# medusa-AI-power.net
KiCad netlist of a schematic drawn in Altium Designer
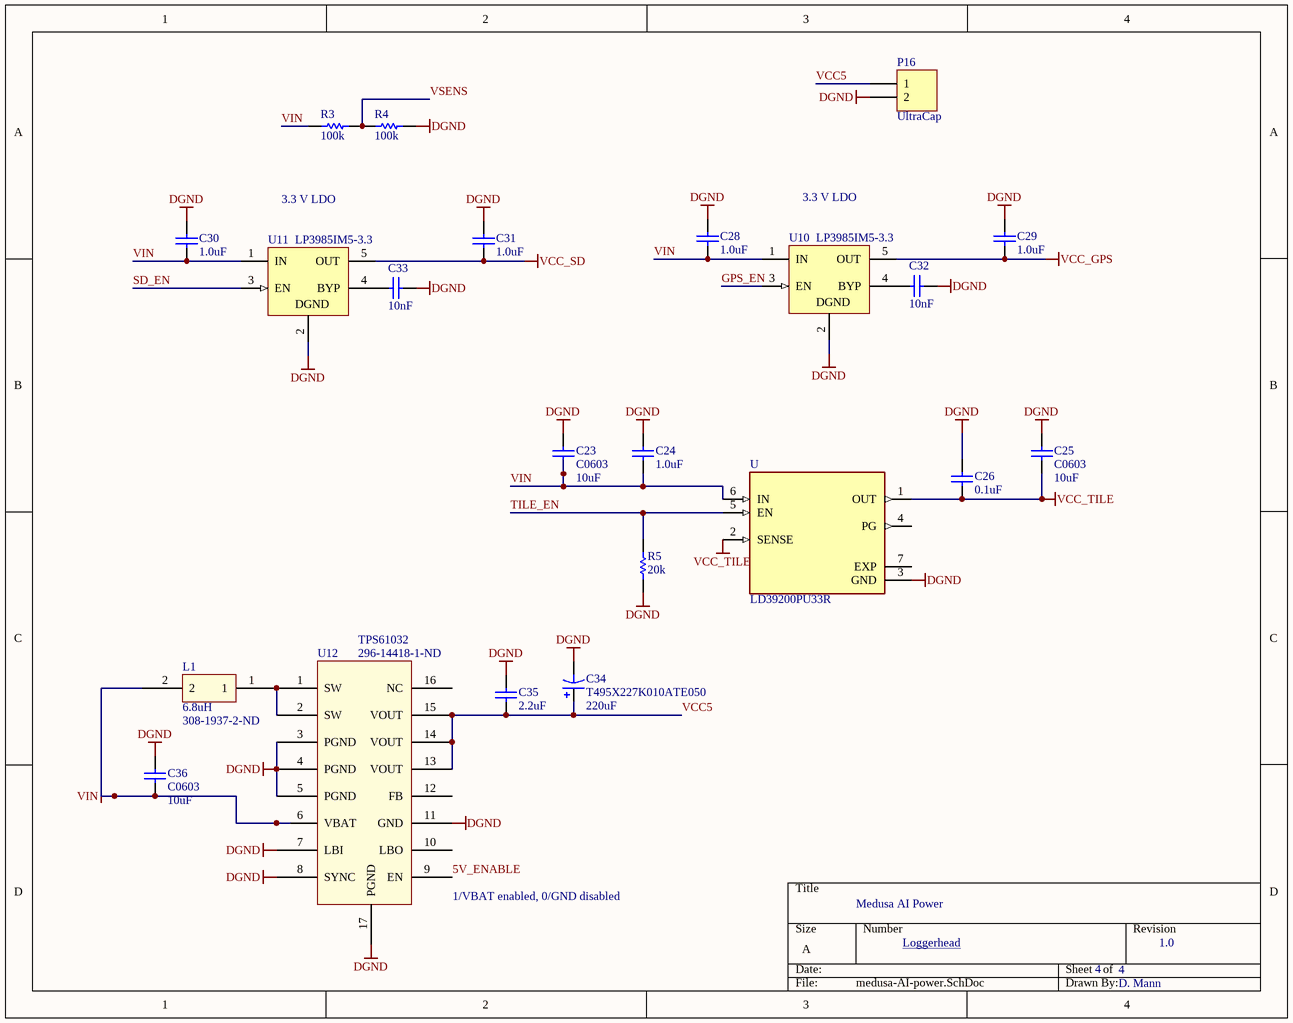
[diagram p0: medusa-AI-power.SchDoc]

(export (version "E")
  (design (tool "Eeschema 10.0.6"))
  (components
    (comp (ref "C23")
      (value "C0603")
      (footprint "0603")
      (description "Ceramic Chip Capacitor - Standard")
      (fields (field (name "ALTIUM_VALUE") "10uF") (field (name "PUBLISHER") "Altium Limited"))
      (libsource (lib "KEMET Chip Capacitor") (part "C0603"))
    )
    (comp (ref "C24")
      (value "1.0uF")
      (footprint "0402")
      (description "Ceramic Chip Capacitor - Standard")
      (fields (field (name "PUBLISHER") "Altium Limited"))
      (libsource (lib "KEMET Chip Capacitor") (part "C0402"))
    )
    (comp (ref "C25")
      (value "C0603")
      (footprint "0603")
      (description "Ceramic Chip Capacitor - Standard")
      (fields (field (name "ALTIUM_VALUE") "10uF") (field (name "PUBLISHER") "Altium Limited"))
      (libsource (lib "KEMET Chip Capacitor") (part "C0603"))
    )
    (comp (ref "C26")
      (value "0.1uF")
      (footprint "0402")
      (description "Ceramic Chip Capacitor - Standard")
      (fields (field (name "PUBLISHER") "Altium Limited"))
      (libsource (lib "KEMET Chip Capacitor") (part "C0402"))
    )
    (comp (ref "C28")
      (value "1.0uF")
      (footprint "0402")
      (description "Ceramic Chip Capacitor - Standard")
      (fields (field (name "PUBLISHER") "Altium Limited"))
      (libsource (lib "KEMET Chip Capacitor") (part "C0402"))
    )
    (comp (ref "C29")
      (value "1.0uF")
      (footprint "0402")
      (description "Ceramic Chip Capacitor - Standard")
      (fields (field (name "PUBLISHER") "Altium Limited"))
      (libsource (lib "KEMET Chip Capacitor") (part "C0402"))
    )
    (comp (ref "C30")
      (value "1.0uF")
      (footprint "0402")
      (description "Ceramic Chip Capacitor - Standard")
      (fields (field (name "PUBLISHER") "Altium Limited"))
      (libsource (lib "KEMET Chip Capacitor") (part "C0402"))
    )
    (comp (ref "C31")
      (value "1.0uF")
      (footprint "0402")
      (description "Ceramic Chip Capacitor - Standard")
      (fields (field (name "PUBLISHER") "Altium Limited"))
      (libsource (lib "KEMET Chip Capacitor") (part "C0402"))
    )
    (comp (ref "C32")
      (value "10nF")
      (footprint "0402")
      (description "Ceramic Chip Capacitor - Standard")
      (fields (field (name "PUBLISHER") "Altium Limited"))
      (libsource (lib "KEMET Chip Capacitor") (part "C0402"))
    )
    (comp (ref "C33")
      (value "10nF")
      (footprint "0402")
      (description "Ceramic Chip Capacitor - Standard")
      (fields (field (name "PUBLISHER") "Altium Limited"))
      (libsource (lib "KEMET Chip Capacitor") (part "C0402"))
    )
    (comp (ref "C34")
      (value "T495X227K010ATE050")
      (footprint "X")
      (description "Solid Tantalum Chip Capacitor, Standard T495 Series - Low ESR, Surge Robust")
      (fields (field (name "ALTIUM_VALUE") "220uF") (field (name "PUBLISHER") "Altium Limited"))
      (libsource (lib "KEMET Chip Capacitor") (part "T495X"))
    )
    (comp (ref "C35")
      (value "2.2uF")
      (footprint "0402")
      (description "Ceramic Chip Capacitor - Standard")
      (fields (field (name "PUBLISHER") "Altium Limited"))
      (libsource (lib "KEMET Chip Capacitor") (part "C0402"))
    )
    (comp (ref "C36")
      (value "C0603")
      (footprint "0603")
      (description "Ceramic Chip Capacitor - Standard")
      (fields (field (name "ALTIUM_VALUE") "10uF") (field (name "PUBLISHER") "Altium Limited"))
      (libsource (lib "KEMET Chip Capacitor") (part "C0603"))
    )
    (comp (ref "L1")
      (value "6.8uH")
      (footprint "Inductor - duplicate")
      (description "Sumida Inductor")
      (fields (field (name "SUPPLIER PART NUMBER 1") "308-1937-2-ND"))
      (libsource (lib "Loggerhead") (part "Inductor 6.8uH"))
    )
    (comp (ref "P16")
      (value "UltraCap")
      (footprint "HDR1X2")
      (description "Header, 2-Pin")
      (fields (field (name "PUBLISHER") "Altium Limited"))
      (libsource (lib "Miscellaneous Connectors") (part "Header 2"))
    )
    (comp (ref "R3")
      (value "100k")
      (footprint "3-0603")
      (fields (field (name "PUBLISHER") "Altium Limited"))
      (libsource (lib "Panasonic Resistor") (part "ERJ3RK"))
    )
    (comp (ref "R4")
      (value "100k")
      (footprint "3-0603")
      (fields (field (name "PUBLISHER") "Altium Limited"))
      (libsource (lib "Panasonic Resistor") (part "ERJ3RK"))
    )
    (comp (ref "R5")
      (value "20k")
      (footprint "3-0603")
      (fields (field (name "PUBLISHER") "Altium Limited"))
      (libsource (lib "Panasonic Resistor") (part "ERJ3RK"))
    )
    (comp (ref "U")
      (value "LD39200PU33R")
      (footprint "SON95P300X300X100-7N")
      (description "Linear Voltage Regulator IC 1 Output 2A 6-DFN _3x3_")
      (fields (field (name "MF") "STMicroelectronics"))
      (libsource (lib "LD39200PU33R") (part "LD39200PU33R"))
    )
    (comp (ref "U10")
      (value "LP3985IM5-3.3")
      (footprint "MF05A_N")
      (description "Micropower, 150mA Low-Noise Ultra Low-Dropout CMOS Voltage Regulator")
      (fields
        (field (name "MANUFACTURER") "National Semiconductor")
        (field (name "DIGIKEYPARTNUMBER") "LP3985IM5-3.3CT-ND")
        (field (name "PUBLISHER") "Altium Limited")
      )
      (libsource (lib "NSC LDO") (part "LP3985IM5-3.3"))
    )
    (comp (ref "U11")
      (value "LP3985IM5-3.3")
      (footprint "MF05A_N")
      (description "Micropower, 150mA Low-Noise Ultra Low-Dropout CMOS Voltage Regulator")
      (fields
        (field (name "MANUFACTURER") "National Semiconductor")
        (field (name "DIGIKEYPARTNUMBER") "LP3985IM5-3.3CT-ND")
        (field (name "PUBLISHER") "Altium Limited")
      )
      (libsource (lib "NSC LDO") (part "LP3985IM5-3.3"))
    )
    (comp (ref "U12")
      (value "TPS61032")
      (footprint "TPS6103x")
      (description "Boost converter")
      (fields (field (name "SUPPLIER PART NUMBER 2") "296-14418-1-ND"))
      (libsource (lib "Loggerhead") (part "TPS6103x"))
    )
  )
  (nets
    (net (code "1") (name "/5V_ENABLE") (class "Default")
      (node (ref "U12") (pin "9") (pinfunction "EN_9") (pintype "passive"))
    )
    (net (code "2") (name "/GPS_EN") (class "Default")
      (node (ref "U10") (pin "3") (pinfunction "EN_3") (pintype "input"))
    )
    (net (code "3") (name "/SD_EN") (class "Default")
      (node (ref "U11") (pin "3") (pinfunction "EN_3") (pintype "input"))
    )
    (net (code "4") (name "/TILE_EN") (class "Default")
      (node (ref "R5") (pin "1") (pinfunction "1_1") (pintype "passive"))
      (node (ref "U") (pin "5") (pinfunction "EN_5") (pintype "input"))
    )
    (net (code "5") (name "/VCC5") (class "Default")
      (node (ref "C34") (pin "1") (pinfunction "1_1") (pintype "passive"))
      (node (ref "C35") (pin "1") (pinfunction "1_1") (pintype "passive"))
      (node (ref "P16") (pin "1") (pinfunction "1_1") (pintype "passive"))
      (node (ref "U12") (pin "13") (pinfunction "VOUT_13") (pintype "passive"))
      (node (ref "U12") (pin "14") (pinfunction "VOUT_14") (pintype "passive"))
      (node (ref "U12") (pin "15") (pinfunction "VOUT_15") (pintype "passive"))
    )
    (net (code "6") (name "/VSENS") (class "Default")
      (node (ref "R3") (pin "1") (pinfunction "1_1") (pintype "passive"))
      (node (ref "R4") (pin "2") (pinfunction "2_2") (pintype "passive"))
    )
    (net (code "7") (name "DGND") (class "Default")
      (node (ref "C23") (pin "1") (pinfunction "1_1") (pintype "passive"))
      (node (ref "C24") (pin "2") (pinfunction "2_2") (pintype "passive"))
      (node (ref "C25") (pin "1") (pinfunction "1_1") (pintype "passive"))
      (node (ref "C26") (pin "2") (pinfunction "2_2") (pintype "passive"))
      (node (ref "C28") (pin "2") (pinfunction "2_2") (pintype "passive"))
      (node (ref "C29") (pin "2") (pinfunction "2_2") (pintype "passive"))
      (node (ref "C30") (pin "2") (pinfunction "2_2") (pintype "passive"))
      (node (ref "C31") (pin "2") (pinfunction "2_2") (pintype "passive"))
      (node (ref "C32") (pin "1") (pinfunction "1_1") (pintype "passive"))
      (node (ref "C33") (pin "1") (pinfunction "1_1") (pintype "passive"))
      (node (ref "C34") (pin "2") (pinfunction "2_2") (pintype "passive"))
      (node (ref "C35") (pin "2") (pinfunction "2_2") (pintype "passive"))
      (node (ref "C36") (pin "1") (pinfunction "1_1") (pintype "passive"))
      (node (ref "P16") (pin "2") (pinfunction "2_2") (pintype "passive"))
      (node (ref "R4") (pin "1") (pinfunction "1_1") (pintype "passive"))
      (node (ref "R5") (pin "2") (pinfunction "2_2") (pintype "passive"))
      (node (ref "U") (pin "3") (pinfunction "GND_3") (pintype "power_in"))
      (node (ref "U10") (pin "2") (pinfunction "GND_2") (pintype "power_in"))
      (node (ref "U11") (pin "2") (pinfunction "GND_2") (pintype "power_in"))
      (node (ref "U12") (pin "11") (pinfunction "GND_11") (pintype "passive"))
      (node (ref "U12") (pin "17") (pinfunction "PGND_17") (pintype "passive"))
      (node (ref "U12") (pin "3") (pinfunction "PGND_3") (pintype "passive"))
      (node (ref "U12") (pin "4") (pinfunction "PGND_4") (pintype "passive"))
      (node (ref "U12") (pin "5") (pinfunction "PGND_5") (pintype "passive"))
      (node (ref "U12") (pin "7") (pinfunction "LBI_7") (pintype "passive"))
      (node (ref "U12") (pin "8") (pinfunction "SYNC_8") (pintype "passive"))
    )
    (net (code "8") (name "Net-(L1-Pad1)") (class "Default")
      (node (ref "L1") (pin "1") (pinfunction "1_1") (pintype "passive"))
      (node (ref "U12") (pin "1") (pinfunction "SW_1") (pintype "passive"))
      (node (ref "U12") (pin "2") (pinfunction "SW_2") (pintype "passive"))
    )
    (net (code "9") (name "Net-(U10-BYP)") (class "Default")
      (node (ref "C32") (pin "2") (pinfunction "2_2") (pintype "passive"))
      (node (ref "U10") (pin "4") (pinfunction "BYP_4") (pintype "passive"))
    )
    (net (code "10") (name "Net-(U11-BYP)") (class "Default")
      (node (ref "C33") (pin "2") (pinfunction "2_2") (pintype "passive"))
      (node (ref "U11") (pin "4") (pinfunction "BYP_4") (pintype "passive"))
    )
    (net (code "11") (name "VCC_GPS") (class "Default")
      (node (ref "C29") (pin "1") (pinfunction "1_1") (pintype "passive"))
      (node (ref "U10") (pin "5") (pinfunction "OUT_5") (pintype "power_in"))
    )
    (net (code "12") (name "VCC_SD") (class "Default")
      (node (ref "C31") (pin "1") (pinfunction "1_1") (pintype "passive"))
      (node (ref "U11") (pin "5") (pinfunction "OUT_5") (pintype "power_in"))
    )
    (net (code "13") (name "VCC_TILE") (class "Default")
      (node (ref "C25") (pin "2") (pinfunction "2_2") (pintype "passive"))
      (node (ref "C26") (pin "1") (pinfunction "1_1") (pintype "passive"))
      (node (ref "U") (pin "1") (pinfunction "OUT_1") (pintype "output"))
      (node (ref "U") (pin "2") (pinfunction "SENSE_2") (pintype "input"))
    )
    (net (code "14") (name "VIN") (class "Default")
      (node (ref "C23") (pin "2") (pinfunction "2_2") (pintype "passive"))
      (node (ref "C24") (pin "1") (pinfunction "1_1") (pintype "passive"))
      (node (ref "C28") (pin "1") (pinfunction "1_1") (pintype "passive"))
      (node (ref "C30") (pin "1") (pinfunction "1_1") (pintype "passive"))
      (node (ref "C36") (pin "2") (pinfunction "2_2") (pintype "passive"))
      (node (ref "L1") (pin "2") (pinfunction "2_2") (pintype "passive"))
      (node (ref "R3") (pin "2") (pinfunction "2_2") (pintype "passive"))
      (node (ref "U") (pin "6") (pinfunction "IN_6") (pintype "input"))
      (node (ref "U10") (pin "1") (pinfunction "IN_1") (pintype "power_in"))
      (node (ref "U11") (pin "1") (pinfunction "IN_1") (pintype "power_in"))
      (node (ref "U12") (pin "6") (pinfunction "VBAT_6") (pintype "passive"))
    )
    (net (code "15") (name "unconnected-(U-EXP-Pad7)") (class "Default")
      (node (ref "U") (pin "7") (pinfunction "EXP_7") (pintype "power_in"))
    )
    (net (code "16") (name "unconnected-(U-PG-Pad4)") (class "Default")
      (node (ref "U") (pin "4") (pinfunction "PG_4") (pintype "output"))
    )
    (net (code "17") (name "unconnected-(U12-FB-Pad12)") (class "Default")
      (node (ref "U12") (pin "12") (pinfunction "FB_12") (pintype "passive"))
    )
    (net (code "18") (name "unconnected-(U12-LBO-Pad10)") (class "Default")
      (node (ref "U12") (pin "10") (pinfunction "LBO_10") (pintype "passive"))
    )
    (net (code "19") (name "unconnected-(U12-NC-Pad16)") (class "Default")
      (node (ref "U12") (pin "16") (pinfunction "NC_16") (pintype "passive"))
    )
  )
)
